# BLE_controller.net
KiCad netlist of a schematic drawn in Altium Designer
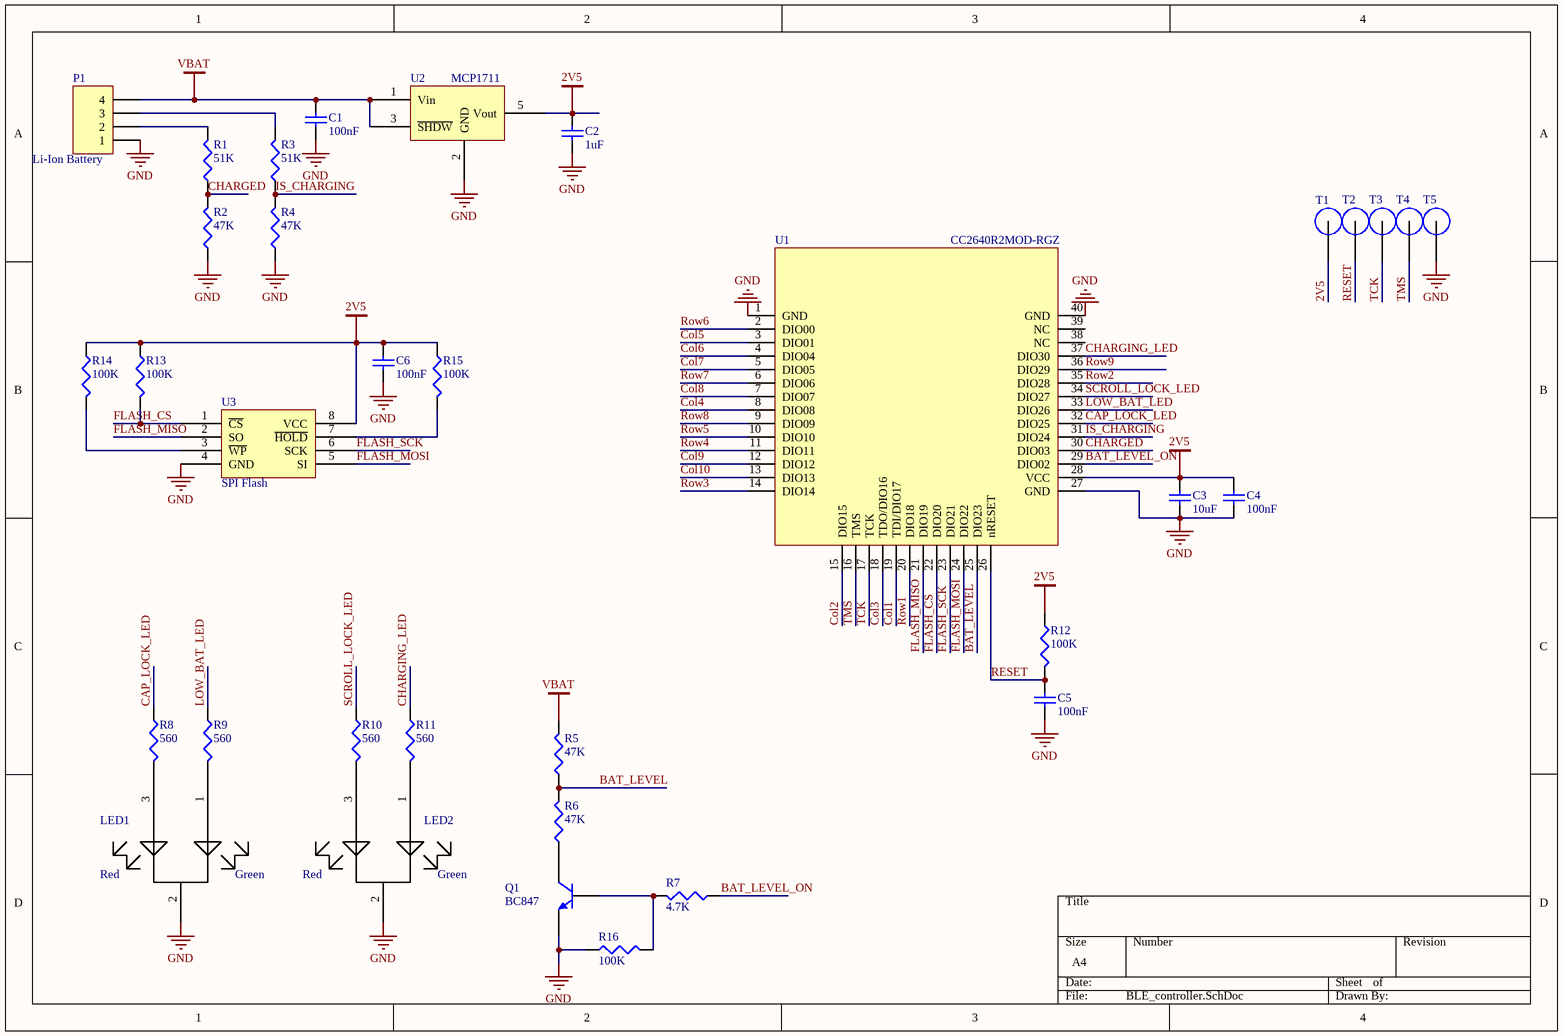
[diagram p0: BLE_controller.SchDoc]

(export (version "E")
  (design (tool "Eeschema 10.0.6"))
  (components
    (comp (ref "C1")
      (value "100nF")
      (footprint "C805_4MOD")
      (description "Capacitor (Semiconductor SIM Model)")
      (fields (field (name "Comment") "Cap Semi") (field (name "PUBLISHER") "Altium Limited"))
      (libsource (lib "Miscellaneous Devices") (part "Cap Semi"))
    )
    (comp (ref "C2")
      (value "1uF")
      (footprint "C805_4MOD")
      (description "Capacitor (Semiconductor SIM Model)")
      (fields (field (name "Comment") "Cap Semi") (field (name "PUBLISHER") "Altium Limited"))
      (libsource (lib "Miscellaneous Devices") (part "Cap Semi"))
    )
    (comp (ref "C3")
      (value "10uF")
      (footprint "C805_4MOD")
      (description "Capacitor (Semiconductor SIM Model)")
      (fields (field (name "Comment") "Cap Semi") (field (name "PUBLISHER") "Altium Limited"))
      (libsource (lib "Miscellaneous Devices") (part "Cap Semi"))
    )
    (comp (ref "C4")
      (value "100nF")
      (footprint "C805_4MOD")
      (description "Capacitor (Semiconductor SIM Model)")
      (fields (field (name "Comment") "Cap Semi") (field (name "PUBLISHER") "Altium Limited"))
      (libsource (lib "Miscellaneous Devices") (part "Cap Semi"))
    )
    (comp (ref "C5")
      (value "100nF")
      (footprint "C805_4MOD")
      (description "Capacitor (Semiconductor SIM Model)")
      (fields (field (name "Comment") "Cap Semi") (field (name "PUBLISHER") "Altium Limited"))
      (libsource (lib "Miscellaneous Devices") (part "Cap Semi"))
    )
    (comp (ref "C6")
      (value "100nF")
      (footprint "C805_4MOD")
      (description "Capacitor (Semiconductor SIM Model)")
      (fields (field (name "Comment") "Cap Semi") (field (name "PUBLISHER") "Altium Limited"))
      (libsource (lib "Miscellaneous Devices") (part "Cap Semi"))
    )
    (comp (ref "LED1")
      (value "Doule_LED_Common_Negative")
      (footprint "Double_LED_Common_Negative")
      (description "209SURSYGW/S530-A3")
      (libsource (lib "BLE_Keyboard_V2") (part "Doule_LED_Common_Negative"))
    )
    (comp (ref "LED2")
      (value "Doule_LED_Common_Negative")
      (footprint "Double_LED_Common_Negative")
      (libsource (lib "BLE_Keyboard_V2") (part "Doule_LED_Common_Negative"))
    )
    (comp (ref "P1")
      (value "Li-Ion Battery")
      (footprint "HDR1X4")
      (description "Header, 4-Pin")
      (fields (field (name "PUBLISHER") "Altium Limited"))
      (libsource (lib "Miscellaneous Connectors") (part "Header 4"))
    )
    (comp (ref "Q1")
      (value "BC847")
      (footprint "SOT23-3")
      (description "NPN General Purpose Amplifier")
      (fields (field (name "PUBLISHER") "Altium Limited"))
      (libsource (lib "Miscellaneous Devices") (part "2N3904"))
    )
    (comp (ref "R1")
      (value "51K")
      (footprint "R805_4MOD")
      (description "Resistor")
      (fields (field (name "Comment") "Res3") (field (name "PUBLISHER") "Altium Limited"))
      (libsource (lib "Miscellaneous Devices") (part "Res3"))
    )
    (comp (ref "R2")
      (value "47K")
      (footprint "R805_4MOD")
      (description "Resistor")
      (fields (field (name "Comment") "Res3") (field (name "PUBLISHER") "Altium Limited"))
      (libsource (lib "Miscellaneous Devices") (part "Res3"))
    )
    (comp (ref "R3")
      (value "51K")
      (footprint "R805_4MOD")
      (description "Resistor")
      (fields (field (name "Comment") "Res3") (field (name "PUBLISHER") "Altium Limited"))
      (libsource (lib "Miscellaneous Devices") (part "Res3"))
    )
    (comp (ref "R4")
      (value "47K")
      (footprint "R805_4MOD")
      (description "Resistor")
      (fields (field (name "Comment") "Res3") (field (name "PUBLISHER") "Altium Limited"))
      (libsource (lib "Miscellaneous Devices") (part "Res3"))
    )
    (comp (ref "R5")
      (value "47K")
      (footprint "R805_4MOD")
      (description "Resistor")
      (fields (field (name "Comment") "Res3") (field (name "PUBLISHER") "Altium Limited"))
      (libsource (lib "Miscellaneous Devices") (part "Res3"))
    )
    (comp (ref "R6")
      (value "47K")
      (footprint "R805_4MOD")
      (description "Resistor")
      (fields (field (name "Comment") "Res3") (field (name "PUBLISHER") "Altium Limited"))
      (libsource (lib "Miscellaneous Devices") (part "Res3"))
    )
    (comp (ref "R7")
      (value "4.7K")
      (footprint "R805_4MOD")
      (description "Resistor")
      (fields (field (name "Comment") "Res3") (field (name "PUBLISHER") "Altium Limited"))
      (libsource (lib "Miscellaneous Devices") (part "Res3"))
    )
    (comp (ref "R8")
      (value "560")
      (footprint "R805_4MOD")
      (description "Resistor")
      (fields (field (name "Comment") "Res3") (field (name "PUBLISHER") "Altium Limited"))
      (libsource (lib "Miscellaneous Devices") (part "Res3"))
    )
    (comp (ref "R9")
      (value "560")
      (footprint "R805_4MOD")
      (description "Resistor")
      (fields (field (name "Comment") "Res3") (field (name "PUBLISHER") "Altium Limited"))
      (libsource (lib "Miscellaneous Devices") (part "Res3"))
    )
    (comp (ref "R10")
      (value "560")
      (footprint "R805_4MOD")
      (description "Resistor")
      (fields (field (name "Comment") "Res3") (field (name "PUBLISHER") "Altium Limited"))
      (libsource (lib "Miscellaneous Devices") (part "Res3"))
    )
    (comp (ref "R11")
      (value "560")
      (footprint "R805_4MOD")
      (description "Resistor")
      (fields (field (name "Comment") "Res3") (field (name "PUBLISHER") "Altium Limited"))
      (libsource (lib "Miscellaneous Devices") (part "Res3"))
    )
    (comp (ref "R12")
      (value "100K")
      (footprint "R805_4MOD")
      (description "Resistor")
      (fields (field (name "Comment") "Res3") (field (name "PUBLISHER") "Altium Limited"))
      (libsource (lib "Miscellaneous Devices") (part "Res3"))
    )
    (comp (ref "R13")
      (value "100K")
      (footprint "R805_4MOD")
      (description "Resistor")
      (fields (field (name "Comment") "Res3") (field (name "PUBLISHER") "Altium Limited"))
      (libsource (lib "Miscellaneous Devices") (part "Res3"))
    )
    (comp (ref "R14")
      (value "100K")
      (footprint "R805_4MOD")
      (description "Resistor")
      (fields (field (name "Comment") "Res3") (field (name "PUBLISHER") "Altium Limited"))
      (libsource (lib "Miscellaneous Devices") (part "Res3"))
    )
    (comp (ref "R15")
      (value "100K")
      (footprint "R805_4MOD")
      (description "Resistor")
      (fields (field (name "Comment") "Res3") (field (name "PUBLISHER") "Altium Limited"))
      (libsource (lib "Miscellaneous Devices") (part "Res3"))
    )
    (comp (ref "R16")
      (value "100K")
      (footprint "R805_4MOD")
      (description "Resistor")
      (fields (field (name "Comment") "Res3") (field (name "PUBLISHER") "Altium Limited"))
      (libsource (lib "Miscellaneous Devices") (part "Res3"))
    )
    (comp (ref "T1")
      (value "Test_Point")
      (footprint "Test_Point")
      (libsource (lib "BLE_Keyboard_V2") (part "Test_Point"))
    )
    (comp (ref "T2")
      (value "Test_Point")
      (footprint "Test_Point")
      (libsource (lib "BLE_Keyboard_V2") (part "Test_Point"))
    )
    (comp (ref "T3")
      (value "Test_Point")
      (footprint "Test_Point")
      (libsource (lib "BLE_Keyboard_V2") (part "Test_Point"))
    )
    (comp (ref "T4")
      (value "Test_Point")
      (footprint "Test_Point")
      (libsource (lib "BLE_Keyboard_V2") (part "Test_Point"))
    )
    (comp (ref "T5")
      (value "Test_Point")
      (footprint "Test_Point")
      (libsource (lib "BLE_Keyboard_V2") (part "Test_Point"))
    )
    (comp (ref "U1")
      (value "CC2640R2MOD-RGZ")
      (footprint "CC26XXMOD-RGZ")
      (description "Ghostyu CC26XX  Module")
      (fields
        (field (name "PART NUMBER") "CC26XXMOD-RGZ")
        (field (name "MANUFACTURER") "Ghostyu")
        (field (name "PART VALUE") "CC2640R2MOD-RGZ")
      )
      (libsource (lib "CC26XXMOD") (part "CC26XXMOD-RGZ"))
    )
    (comp (ref "U2") (value "MCP1711") (footprint "LC-SOT-23-5") (libsource (lib "Schlib1") (part "MCP1711")))
    (comp (ref "U3")
      (value "SPI Flash")
      (footprint "LC-SOIC-8_150mil")
      (libsource (lib "BLE_Keyboard_V2") (part "AT25XE021A_SOIC-8"))
    )
  )
  (nets
    (net (code "1") (name "/BAT_LEVEL") (class "Default")
      (node (ref "R5") (pin "1") (pinfunction "1_1") (pintype "passive"))
      (node (ref "R6") (pin "2") (pinfunction "2_2") (pintype "passive"))
      (node (ref "U1") (pin "25") (pinfunction "DIO23_25") (pintype "passive"))
    )
    (net (code "2") (name "/BAT_LEVEL_ON") (class "Default")
      (node (ref "R7") (pin "1") (pinfunction "1_1") (pintype "passive"))
      (node (ref "U1") (pin "29") (pinfunction "DIO02_29") (pintype "passive"))
    )
    (net (code "3") (name "/CAP_LOCK_LED") (class "Default")
      (node (ref "R8") (pin "1") (pinfunction "1_1") (pintype "passive"))
      (node (ref "U1") (pin "32") (pinfunction "DIO25_32") (pintype "passive"))
    )
    (net (code "4") (name "/CHARGED") (class "Default")
      (node (ref "R1") (pin "1") (pinfunction "1_1") (pintype "passive"))
      (node (ref "R2") (pin "2") (pinfunction "2_2") (pintype "passive"))
      (node (ref "U1") (pin "30") (pinfunction "DIO03_30") (pintype "passive"))
    )
    (net (code "5") (name "/CHARGING_LED") (class "Default")
      (node (ref "R11") (pin "1") (pinfunction "1_1") (pintype "passive"))
      (node (ref "U1") (pin "37") (pinfunction "DIO30_37") (pintype "passive"))
    )
    (net (code "6") (name "/Col1") (class "Default")
      (node (ref "U1") (pin "19") (pinfunction "TDI/DIO17_19") (pintype "passive"))
    )
    (net (code "7") (name "/Col2") (class "Default")
      (node (ref "U1") (pin "15") (pinfunction "DIO15_15") (pintype "passive"))
    )
    (net (code "8") (name "/Col3") (class "Default")
      (node (ref "U1") (pin "18") (pinfunction "TDO/DIO16_18") (pintype "passive"))
    )
    (net (code "9") (name "/Col4") (class "Default")
      (node (ref "U1") (pin "8") (pinfunction "DIO08_8") (pintype "passive"))
    )
    (net (code "10") (name "/Col5") (class "Default")
      (node (ref "U1") (pin "3") (pinfunction "DIO01_3") (pintype "passive"))
    )
    (net (code "11") (name "/Col6") (class "Default")
      (node (ref "U1") (pin "4") (pinfunction "DIO04_4") (pintype "passive"))
    )
    (net (code "12") (name "/Col7") (class "Default")
      (node (ref "U1") (pin "5") (pinfunction "DIO05_5") (pintype "passive"))
    )
    (net (code "13") (name "/Col8") (class "Default")
      (node (ref "U1") (pin "7") (pinfunction "DIO07_7") (pintype "passive"))
    )
    (net (code "14") (name "/Col9") (class "Default")
      (node (ref "U1") (pin "12") (pinfunction "DIO12_12") (pintype "passive"))
    )
    (net (code "15") (name "/Col10") (class "Default")
      (node (ref "U1") (pin "13") (pinfunction "DIO13_13") (pintype "passive"))
    )
    (net (code "16") (name "/FLASH_CS") (class "Default")
      (node (ref "R13") (pin "2") (pinfunction "2_2") (pintype "passive"))
      (node (ref "U1") (pin "22") (pinfunction "DIO20_22") (pintype "passive"))
      (node (ref "U3") (pin "1") (pinfunction "~{CS}_1") (pintype "passive"))
    )
    (net (code "17") (name "/FLASH_MISO") (class "Default")
      (node (ref "U1") (pin "21") (pinfunction "DIO19_21") (pintype "passive"))
      (node (ref "U3") (pin "2") (pinfunction "SO_2") (pintype "passive"))
    )
    (net (code "18") (name "/FLASH_MOSI") (class "Default")
      (node (ref "U1") (pin "24") (pinfunction "DIO22_24") (pintype "passive"))
      (node (ref "U3") (pin "5") (pinfunction "SI_5") (pintype "passive"))
    )
    (net (code "19") (name "/FLASH_SCK") (class "Default")
      (node (ref "U1") (pin "23") (pinfunction "DIO21_23") (pintype "passive"))
      (node (ref "U3") (pin "6") (pinfunction "SCK_6") (pintype "passive"))
    )
    (net (code "20") (name "/IS_CHARGING") (class "Default")
      (node (ref "R3") (pin "1") (pinfunction "1_1") (pintype "passive"))
      (node (ref "R4") (pin "2") (pinfunction "2_2") (pintype "passive"))
      (node (ref "U1") (pin "31") (pinfunction "DIO24_31") (pintype "passive"))
    )
    (net (code "21") (name "/LOW_BAT_LED") (class "Default")
      (node (ref "R9") (pin "1") (pinfunction "1_1") (pintype "passive"))
      (node (ref "U1") (pin "33") (pinfunction "DIO26_33") (pintype "passive"))
    )
    (net (code "22") (name "/RESET") (class "Default")
      (node (ref "C5") (pin "2") (pinfunction "2_2") (pintype "passive"))
      (node (ref "R12") (pin "2") (pinfunction "2_2") (pintype "passive"))
      (node (ref "T2") (pin "1") (pintype "passive"))
      (node (ref "U1") (pin "26") (pinfunction "nRESET_26") (pintype "passive"))
    )
    (net (code "23") (name "/Row1") (class "Default")
      (node (ref "U1") (pin "20") (pinfunction "DIO18_20") (pintype "passive"))
    )
    (net (code "24") (name "/Row2") (class "Default")
      (node (ref "U1") (pin "35") (pinfunction "DIO28_35") (pintype "passive"))
    )
    (net (code "25") (name "/Row3") (class "Default")
      (node (ref "U1") (pin "14") (pinfunction "DIO14_14") (pintype "passive"))
    )
    (net (code "26") (name "/Row4") (class "Default")
      (node (ref "U1") (pin "11") (pinfunction "DIO11_11") (pintype "passive"))
    )
    (net (code "27") (name "/Row5") (class "Default")
      (node (ref "U1") (pin "10") (pinfunction "DIO10_10") (pintype "passive"))
    )
    (net (code "28") (name "/Row6") (class "Default")
      (node (ref "U1") (pin "2") (pinfunction "DIO00_2") (pintype "passive"))
    )
    (net (code "29") (name "/Row7") (class "Default")
      (node (ref "U1") (pin "6") (pinfunction "DIO06_6") (pintype "passive"))
    )
    (net (code "30") (name "/Row8") (class "Default")
      (node (ref "U1") (pin "9") (pinfunction "DIO09_9") (pintype "passive"))
    )
    (net (code "31") (name "/Row9") (class "Default")
      (node (ref "U1") (pin "36") (pinfunction "DIO29_36") (pintype "passive"))
    )
    (net (code "32") (name "/SCROLL_LOCK_LED") (class "Default")
      (node (ref "R10") (pin "1") (pinfunction "1_1") (pintype "passive"))
      (node (ref "U1") (pin "34") (pinfunction "DIO27_34") (pintype "passive"))
    )
    (net (code "33") (name "/TCK") (class "Default")
      (node (ref "T3") (pin "1") (pintype "passive"))
      (node (ref "U1") (pin "17") (pinfunction "TCK_17") (pintype "passive"))
    )
    (net (code "34") (name "/TMS") (class "Default")
      (node (ref "T4") (pin "1") (pintype "passive"))
      (node (ref "U1") (pin "16") (pinfunction "TMS_16") (pintype "passive"))
    )
    (net (code "35") (name "2V5") (class "Default")
      (node (ref "C2") (pin "2") (pinfunction "2_2") (pintype "passive"))
      (node (ref "C3") (pin "2") (pinfunction "2_2") (pintype "passive"))
      (node (ref "C4") (pin "2") (pinfunction "2_2") (pintype "passive"))
      (node (ref "C6") (pin "2") (pinfunction "2_2") (pintype "passive"))
      (node (ref "R12") (pin "1") (pinfunction "1_1") (pintype "passive"))
      (node (ref "R13") (pin "1") (pinfunction "1_1") (pintype "passive"))
      (node (ref "R14") (pin "1") (pinfunction "1_1") (pintype "passive"))
      (node (ref "R15") (pin "1") (pinfunction "1_1") (pintype "passive"))
      (node (ref "T1") (pin "1") (pintype "passive"))
      (node (ref "U1") (pin "28") (pinfunction "VCC_28") (pintype "passive"))
      (node (ref "U2") (pin "5") (pinfunction "Vout_5") (pintype "passive"))
      (node (ref "U3") (pin "8") (pinfunction "VCC_8") (pintype "passive"))
    )
    (net (code "36") (name "GND") (class "Default")
      (node (ref "C1") (pin "1") (pinfunction "1_1") (pintype "passive"))
      (node (ref "C2") (pin "1") (pinfunction "1_1") (pintype "passive"))
      (node (ref "C3") (pin "1") (pinfunction "1_1") (pintype "passive"))
      (node (ref "C4") (pin "1") (pinfunction "1_1") (pintype "passive"))
      (node (ref "C5") (pin "1") (pinfunction "1_1") (pintype "passive"))
      (node (ref "C6") (pin "1") (pinfunction "1_1") (pintype "passive"))
      (node (ref "LED1") (pin "2") (pinfunction "2_2") (pintype "passive"))
      (node (ref "LED2") (pin "2") (pinfunction "2_2") (pintype "passive"))
      (node (ref "P1") (pin "1") (pinfunction "1_1") (pintype "passive"))
      (node (ref "Q1") (pin "2") (pinfunction "E_2") (pintype "passive"))
      (node (ref "R16") (pin "1") (pinfunction "1_1") (pintype "passive"))
      (node (ref "R2") (pin "1") (pinfunction "1_1") (pintype "passive"))
      (node (ref "R4") (pin "1") (pinfunction "1_1") (pintype "passive"))
      (node (ref "T5") (pin "1") (pintype "passive"))
      (node (ref "U1") (pin "1") (pinfunction "GND_1") (pintype "passive"))
      (node (ref "U1") (pin "27") (pinfunction "GND_27") (pintype "passive"))
      (node (ref "U1") (pin "40") (pinfunction "GND_40") (pintype "passive"))
      (node (ref "U2") (pin "2") (pinfunction "GND_2") (pintype "passive"))
      (node (ref "U3") (pin "4") (pinfunction "GND_4") (pintype "passive"))
    )
    (net (code "37") (name "Net-(LED1-Pad1)") (class "Default")
      (node (ref "LED1") (pin "1") (pinfunction "1_1") (pintype "passive"))
      (node (ref "R9") (pin "2") (pinfunction "2_2") (pintype "passive"))
    )
    (net (code "38") (name "Net-(LED1-Pad3)") (class "Default")
      (node (ref "LED1") (pin "3") (pintype "passive"))
      (node (ref "R8") (pin "2") (pinfunction "2_2") (pintype "passive"))
    )
    (net (code "39") (name "Net-(LED2-Pad1)") (class "Default")
      (node (ref "LED2") (pin "1") (pinfunction "1_1") (pintype "passive"))
      (node (ref "R11") (pin "2") (pinfunction "2_2") (pintype "passive"))
    )
    (net (code "40") (name "Net-(LED2-Pad3)") (class "Default")
      (node (ref "LED2") (pin "3") (pintype "passive"))
      (node (ref "R10") (pin "2") (pinfunction "2_2") (pintype "passive"))
    )
    (net (code "41") (name "Net-(P1-Pad2)") (class "Default")
      (node (ref "P1") (pin "2") (pinfunction "2_2") (pintype "passive"))
      (node (ref "R1") (pin "2") (pinfunction "2_2") (pintype "passive"))
    )
    (net (code "42") (name "Net-(P1-Pad3)") (class "Default")
      (node (ref "P1") (pin "3") (pinfunction "3_3") (pintype "passive"))
      (node (ref "R3") (pin "2") (pinfunction "2_2") (pintype "passive"))
    )
    (net (code "43") (name "Net-(Q1-B)") (class "Default")
      (node (ref "Q1") (pin "1") (pinfunction "B_1") (pintype "passive"))
      (node (ref "R16") (pin "2") (pinfunction "2_2") (pintype "passive"))
      (node (ref "R7") (pin "2") (pinfunction "2_2") (pintype "passive"))
    )
    (net (code "44") (name "Net-(Q1-C)") (class "Default")
      (node (ref "Q1") (pin "3") (pinfunction "C_3") (pintype "passive"))
      (node (ref "R6") (pin "1") (pinfunction "1_1") (pintype "passive"))
    )
    (net (code "45") (name "Net-(U3-~{HOLD})") (class "Default")
      (node (ref "R15") (pin "2") (pinfunction "2_2") (pintype "passive"))
      (node (ref "U3") (pin "7") (pinfunction "~{HOLD}_7") (pintype "passive"))
    )
    (net (code "46") (name "Net-(U3-~{WP})") (class "Default")
      (node (ref "R14") (pin "2") (pinfunction "2_2") (pintype "passive"))
      (node (ref "U3") (pin "3") (pinfunction "~{WP}_3") (pintype "passive"))
    )
    (net (code "47") (name "VBAT") (class "Default")
      (node (ref "C1") (pin "2") (pinfunction "2_2") (pintype "passive"))
      (node (ref "P1") (pin "4") (pinfunction "4_4") (pintype "passive"))
      (node (ref "R5") (pin "2") (pinfunction "2_2") (pintype "passive"))
      (node (ref "U2") (pin "1") (pinfunction "Vin_1") (pintype "passive"))
      (node (ref "U2") (pin "3") (pinfunction "~{SHDW}_3") (pintype "passive"))
    )
    (net (code "48") (name "unconnected-(U1-NC-Pad38)") (class "Default")
      (node (ref "U1") (pin "38") (pinfunction "NC_38") (pintype "passive"))
    )
    (net (code "49") (name "unconnected-(U1-NC-Pad39)") (class "Default")
      (node (ref "U1") (pin "39") (pinfunction "NC_39") (pintype "passive"))
    )
  )
)
